# Motor_Driver_Sheet.net
KiCad netlist of a schematic drawn in Altium Designer
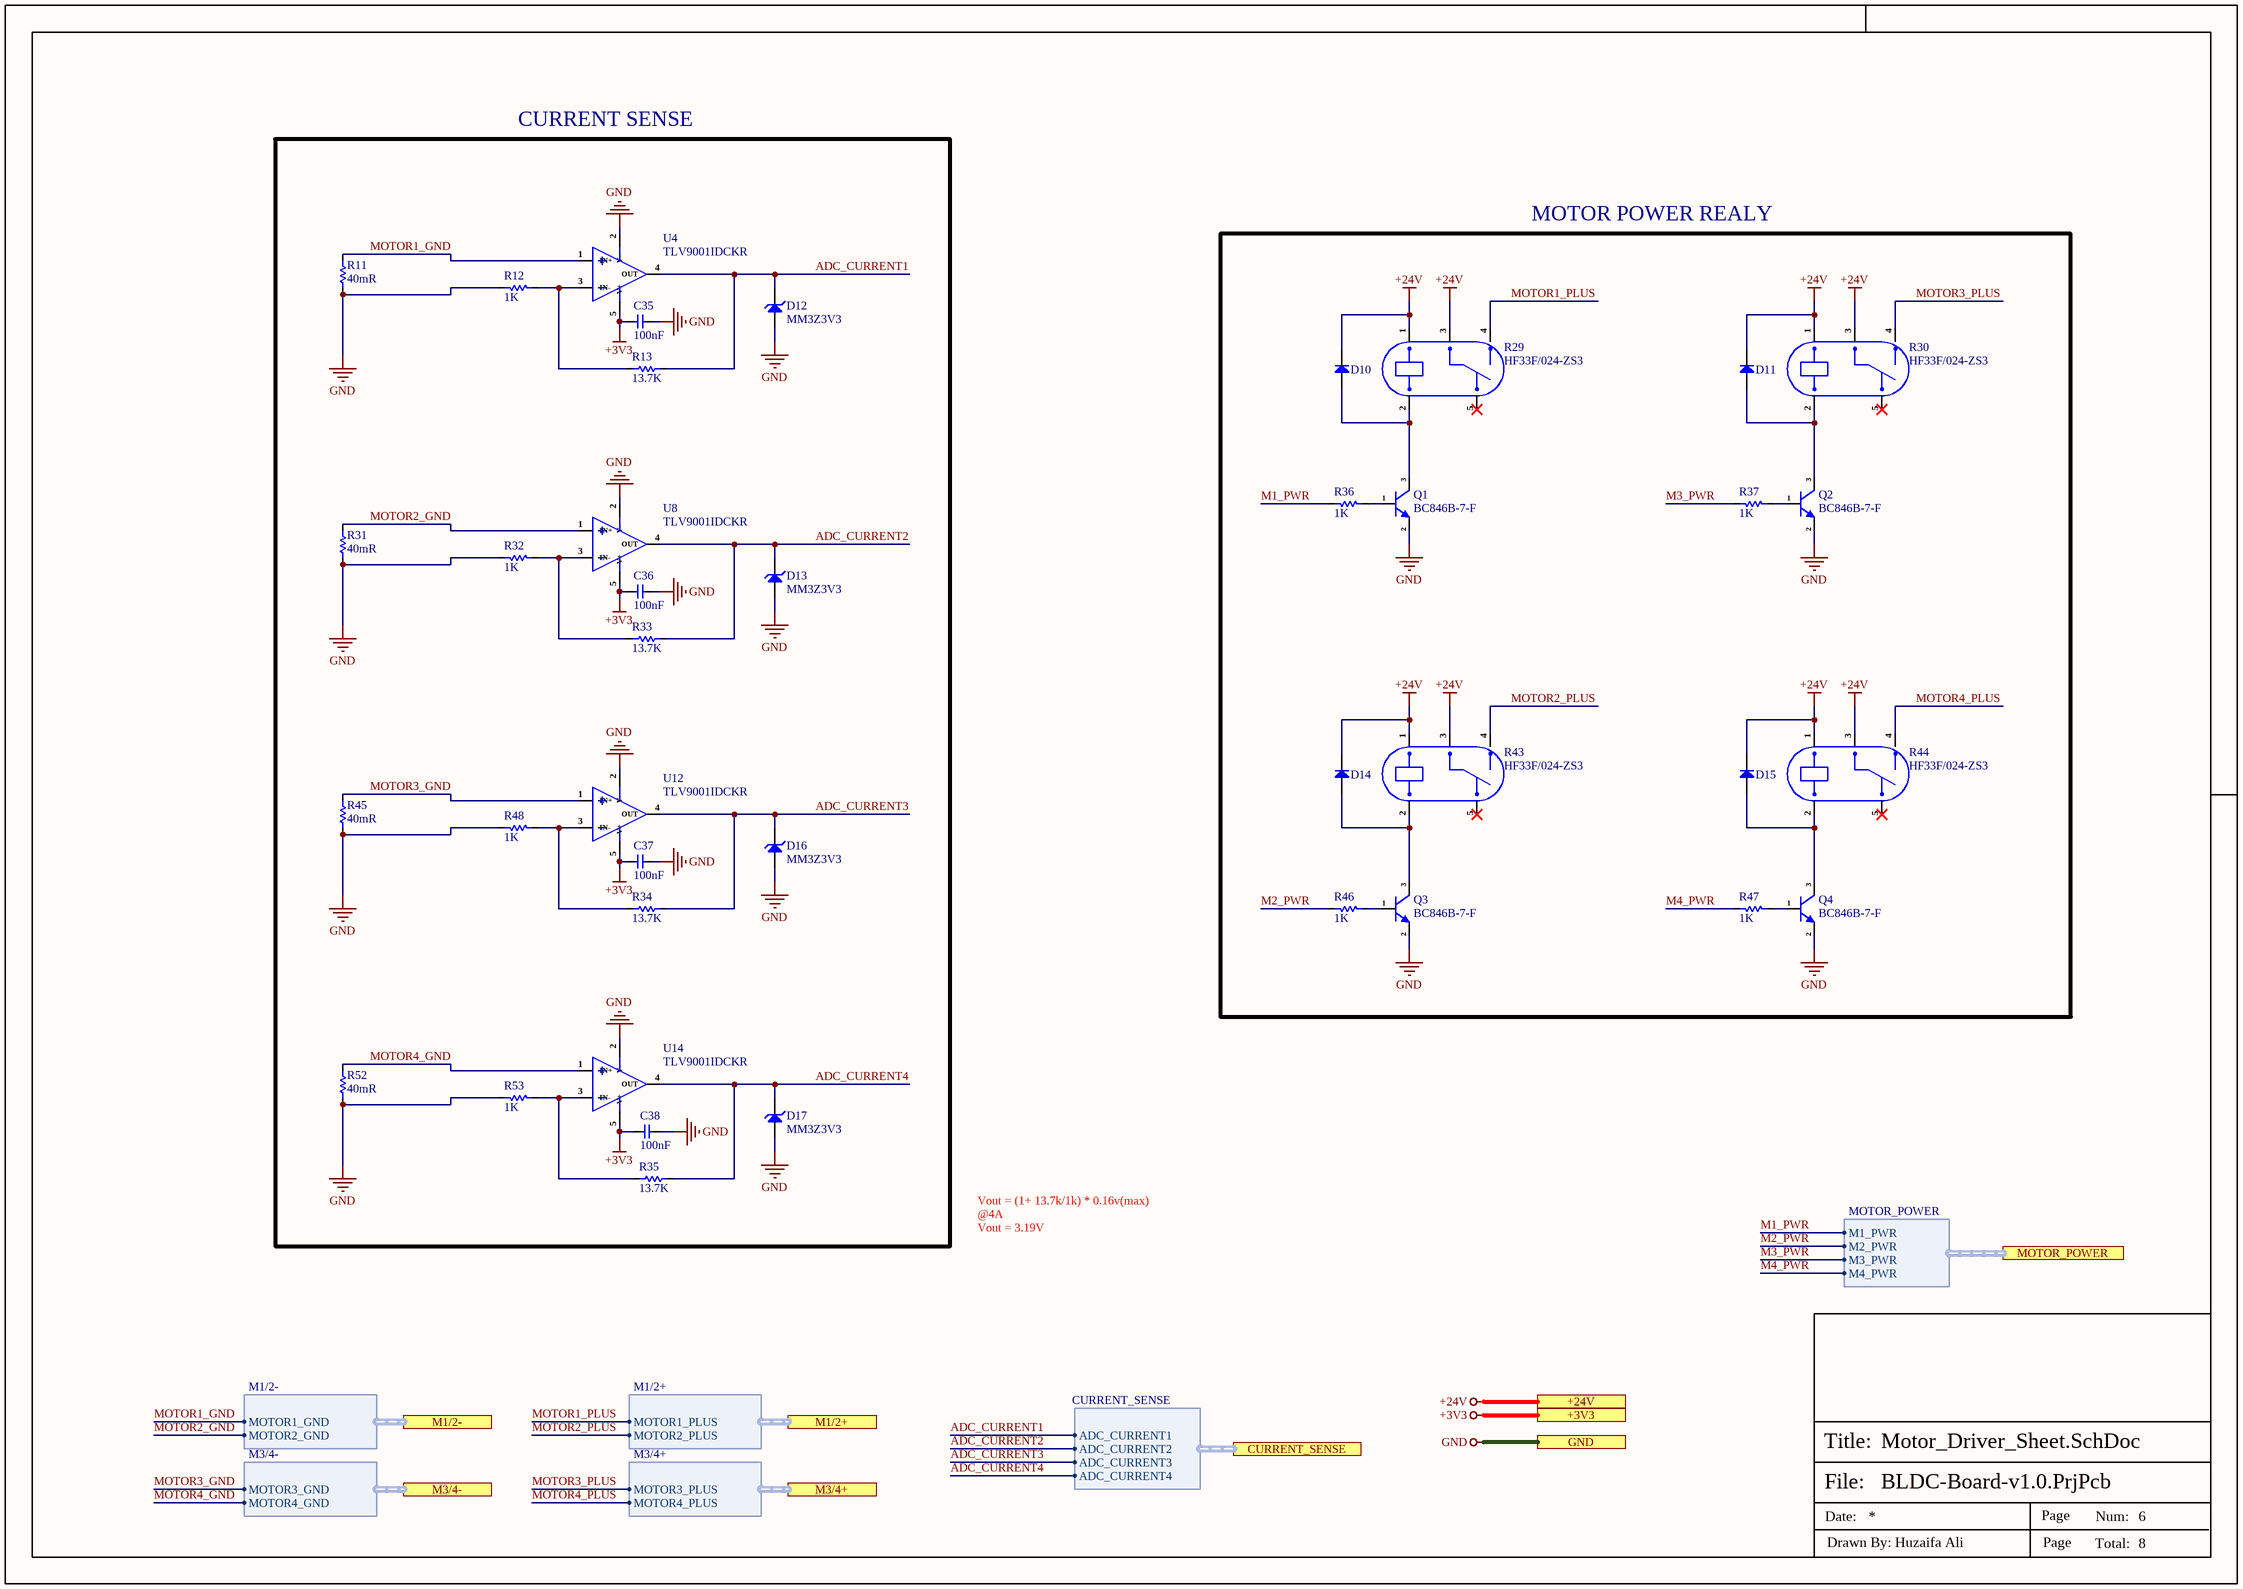
[diagram p0: Motor_Driver_Sheet.SchDoc]

(export (version "E")
  (design (tool "Eeschema 10.0.6"))
  (components
    (comp (ref "C35")
      (value "100nF")
      (footprint "cap-0402")
      (description "CAP CER 0.1UF 50V X7R 0402")
      (fields
        (field (name "MANUFACTURER") "TDK")
        (field (name "MANUFACTURER PART NUMBER") "C1005X7R1H104KT000F")
      )
      (libsource (lib "eSpark Libraries") (part "C1005X7R1H104KT000F"))
    )
    (comp (ref "C36")
      (value "100nF")
      (footprint "cap-0402")
      (description "CAP CER 0.1UF 50V X7R 0402")
      (fields
        (field (name "MANUFACTURER") "TDK")
        (field (name "MANUFACTURER PART NUMBER") "C1005X7R1H104KT000F")
      )
      (libsource (lib "eSpark Libraries") (part "C1005X7R1H104KT000F"))
    )
    (comp (ref "C37")
      (value "100nF")
      (footprint "cap-0402")
      (description "CAP CER 0.1UF 50V X7R 0402")
      (fields
        (field (name "MANUFACTURER") "TDK")
        (field (name "MANUFACTURER PART NUMBER") "C1005X7R1H104KT000F")
      )
      (libsource (lib "eSpark Libraries") (part "C1005X7R1H104KT000F"))
    )
    (comp (ref "C38")
      (value "100nF")
      (footprint "cap-0402")
      (description "CAP CER 0.1UF 50V X7R 0402")
      (fields
        (field (name "MANUFACTURER") "TDK")
        (field (name "MANUFACTURER PART NUMBER") "C1005X7R1H104KT000F")
      )
      (libsource (lib "eSpark Libraries") (part "C1005X7R1H104KT000F"))
    )
    (comp (ref "D10")
      (value "1N4148WS-7-F")
      (footprint "SOD-323")
      (description "DIODE GEN PURP 75V 150MA SOD323")
      (fields (field (name "MANUFACTURER") "Diodes") (field (name "VOLTAGE") "75V"))
      (libsource (lib "eSpark Libraries") (part "1N4148WS-7-F"))
    )
    (comp (ref "D11")
      (value "1N4148WS-7-F")
      (footprint "SOD-323")
      (description "DIODE GEN PURP 75V 150MA SOD323")
      (fields (field (name "MANUFACTURER") "Diodes") (field (name "VOLTAGE") "75V"))
      (libsource (lib "eSpark Libraries") (part "1N4148WS-7-F"))
    )
    (comp (ref "D12")
      (value "MM3Z3V3")
      (footprint "SOD-323")
      (description "±5% Single 3.1V~3.5V 300mW 3.3V SOD-323 Zener Diodes ROHS")
      (fields (field (name "MANUFACTURER") "JSMSEMI") (field (name "LCSC PART NUMBER") "C123917"))
      (libsource (lib "eSpark Libraries") (part "MM3Z3V3"))
    )
    (comp (ref "D13")
      (value "MM3Z3V3")
      (footprint "SOD-323")
      (description "±5% Single 3.1V~3.5V 300mW 3.3V SOD-323 Zener Diodes ROHS")
      (fields (field (name "MANUFACTURER") "JSMSEMI") (field (name "LCSC PART NUMBER") "C123917"))
      (libsource (lib "eSpark Libraries") (part "MM3Z3V3"))
    )
    (comp (ref "D14")
      (value "1N4148WS-7-F")
      (footprint "SOD-323")
      (description "DIODE GEN PURP 75V 150MA SOD323")
      (fields (field (name "MANUFACTURER") "Diodes") (field (name "VOLTAGE") "75V"))
      (libsource (lib "eSpark Libraries") (part "1N4148WS-7-F"))
    )
    (comp (ref "D15")
      (value "1N4148WS-7-F")
      (footprint "SOD-323")
      (description "DIODE GEN PURP 75V 150MA SOD323")
      (fields (field (name "MANUFACTURER") "Diodes") (field (name "VOLTAGE") "75V"))
      (libsource (lib "eSpark Libraries") (part "1N4148WS-7-F"))
    )
    (comp (ref "D16")
      (value "MM3Z3V3")
      (footprint "SOD-323")
      (description "±5% Single 3.1V~3.5V 300mW 3.3V SOD-323 Zener Diodes ROHS")
      (fields (field (name "MANUFACTURER") "JSMSEMI") (field (name "LCSC PART NUMBER") "C123917"))
      (libsource (lib "eSpark Libraries") (part "MM3Z3V3"))
    )
    (comp (ref "D17")
      (value "MM3Z3V3")
      (footprint "SOD-323")
      (description "±5% Single 3.1V~3.5V 300mW 3.3V SOD-323 Zener Diodes ROHS")
      (fields (field (name "MANUFACTURER") "JSMSEMI") (field (name "LCSC PART NUMBER") "C123917"))
      (libsource (lib "eSpark Libraries") (part "MM3Z3V3"))
    )
    (comp (ref "Q1")
      (value "BC846B-7-F")
      (footprint "SOT-23")
      (description "TRANS NPN 65V 0.1A SOT23-3")
      (fields (field (name "MANUFACTURER") "Diodes") (field (name "LCSC PART NUMBER") "C183643"))
      (libsource (lib "eSpark Libraries") (part "BC846B-7-F"))
    )
    (comp (ref "Q2")
      (value "BC846B-7-F")
      (footprint "SOT-23")
      (description "TRANS NPN 65V 0.1A SOT23-3")
      (fields (field (name "MANUFACTURER") "Diodes") (field (name "LCSC PART NUMBER") "C183643"))
      (libsource (lib "eSpark Libraries") (part "BC846B-7-F"))
    )
    (comp (ref "Q3")
      (value "BC846B-7-F")
      (footprint "SOT-23")
      (description "TRANS NPN 65V 0.1A SOT23-3")
      (fields (field (name "MANUFACTURER") "Diodes") (field (name "LCSC PART NUMBER") "C183643"))
      (libsource (lib "eSpark Libraries") (part "BC846B-7-F"))
    )
    (comp (ref "Q4")
      (value "BC846B-7-F")
      (footprint "SOT-23")
      (description "TRANS NPN 65V 0.1A SOT23-3")
      (fields (field (name "MANUFACTURER") "Diodes") (field (name "LCSC PART NUMBER") "C183643"))
      (libsource (lib "eSpark Libraries") (part "BC846B-7-F"))
    )
    (comp (ref "R11")
      (value "40mR")
      (footprint "Res-1206")
      (fields
        (field (name "MANUFACTURER") "RALEC")
        (field (name "MANUFACTURER PART NUMBER") "LR1206-21R040F4")
        (field (name "LCSC PART NUMBER") "C2681030")
      )
      (libsource (lib "eSpark Libraries") (part "LR1206-21R040F4"))
    )
    (comp (ref "R12")
      (value "1K")
      (footprint "Res-0402")
      (description "RES SMD 1K OHM 1% 1/5W 0402")
      (fields
        (field (name "MANUFACTURER") "Vishay Dale")
        (field (name "MANUFACTURER PART NUMBER") "CRCW04021K00FKEDHP")
      )
      (libsource (lib "eSpark Libraries") (part "CRCW04021K00FKEDHP"))
    )
    (comp (ref "R13")
      (value "13.7K")
      (footprint "Res-0603")
      (description "RES SMD 13.7KOHM 0.1% 1/10W 0603")
      (fields
        (field (name "MANUFACTURER") "Yageo")
        (field (name "MANUFACTURER PART NUMBER") "AT0603BRD0713K7L")
      )
      (libsource (lib "eSpark Libraries") (part "AT0603BRD0713K7L"))
    )
    (comp (ref "R29")
      (value "HF33F/024-ZS3")
      (footprint "HF33F/024-ZS3")
      (description "24V 10A SPDT (1 Form C) Plugin,10.2x20.5mm Power Relays ROHS")
      (fields
        (field (name "MANUFACTURER") "HF(Xiamen Hongfa Electroacoustic)")
        (field (name "LCSC PART NUMBER") "C36391")
      )
      (libsource (lib "eSpark Libraries") (part "HF33F/024-ZS3"))
    )
    (comp (ref "R30")
      (value "HF33F/024-ZS3")
      (footprint "HF33F/024-ZS3")
      (description "24V 10A SPDT (1 Form C) Plugin,10.2x20.5mm Power Relays ROHS")
      (fields
        (field (name "MANUFACTURER") "HF(Xiamen Hongfa Electroacoustic)")
        (field (name "LCSC PART NUMBER") "C36391")
      )
      (libsource (lib "eSpark Libraries") (part "HF33F/024-ZS3"))
    )
    (comp (ref "R31")
      (value "40mR")
      (footprint "Res-1206")
      (fields
        (field (name "MANUFACTURER") "RALEC")
        (field (name "MANUFACTURER PART NUMBER") "LR1206-21R040F4")
        (field (name "LCSC PART NUMBER") "C2681030")
      )
      (libsource (lib "eSpark Libraries") (part "LR1206-21R040F4"))
    )
    (comp (ref "R32")
      (value "1K")
      (footprint "Res-0402")
      (description "RES SMD 1K OHM 1% 1/5W 0402")
      (fields
        (field (name "MANUFACTURER") "Vishay Dale")
        (field (name "MANUFACTURER PART NUMBER") "CRCW04021K00FKEDHP")
      )
      (libsource (lib "eSpark Libraries") (part "CRCW04021K00FKEDHP"))
    )
    (comp (ref "R33")
      (value "13.7K")
      (footprint "Res-0603")
      (description "RES SMD 13.7KOHM 0.1% 1/10W 0603")
      (fields
        (field (name "MANUFACTURER") "Yageo")
        (field (name "MANUFACTURER PART NUMBER") "AT0603BRD0713K7L")
      )
      (libsource (lib "eSpark Libraries") (part "AT0603BRD0713K7L"))
    )
    (comp (ref "R34")
      (value "13.7K")
      (footprint "Res-0603")
      (description "RES SMD 13.7KOHM 0.1% 1/10W 0603")
      (fields
        (field (name "MANUFACTURER") "Yageo")
        (field (name "MANUFACTURER PART NUMBER") "AT0603BRD0713K7L")
      )
      (libsource (lib "eSpark Libraries") (part "AT0603BRD0713K7L"))
    )
    (comp (ref "R35")
      (value "13.7K")
      (footprint "Res-0603")
      (description "RES SMD 13.7KOHM 0.1% 1/10W 0603")
      (fields
        (field (name "MANUFACTURER") "Yageo")
        (field (name "MANUFACTURER PART NUMBER") "AT0603BRD0713K7L")
      )
      (libsource (lib "eSpark Libraries") (part "AT0603BRD0713K7L"))
    )
    (comp (ref "R36")
      (value "1K")
      (footprint "Res-0402")
      (description "RES SMD 1K OHM 1% 1/5W 0402")
      (fields
        (field (name "MANUFACTURER") "Vishay Dale")
        (field (name "MANUFACTURER PART NUMBER") "CRCW04021K00FKEDHP")
      )
      (libsource (lib "eSpark Libraries") (part "CRCW04021K00FKEDHP"))
    )
    (comp (ref "R37")
      (value "1K")
      (footprint "Res-0402")
      (description "RES SMD 1K OHM 1% 1/5W 0402")
      (fields
        (field (name "MANUFACTURER") "Vishay Dale")
        (field (name "MANUFACTURER PART NUMBER") "CRCW04021K00FKEDHP")
      )
      (libsource (lib "eSpark Libraries") (part "CRCW04021K00FKEDHP"))
    )
    (comp (ref "R43")
      (value "HF33F/024-ZS3")
      (footprint "HF33F/024-ZS3")
      (description "24V 10A SPDT (1 Form C) Plugin,10.2x20.5mm Power Relays ROHS")
      (fields
        (field (name "MANUFACTURER") "HF(Xiamen Hongfa Electroacoustic)")
        (field (name "LCSC PART NUMBER") "C36391")
      )
      (libsource (lib "eSpark Libraries") (part "HF33F/024-ZS3"))
    )
    (comp (ref "R44")
      (value "HF33F/024-ZS3")
      (footprint "HF33F/024-ZS3")
      (description "24V 10A SPDT (1 Form C) Plugin,10.2x20.5mm Power Relays ROHS")
      (fields
        (field (name "MANUFACTURER") "HF(Xiamen Hongfa Electroacoustic)")
        (field (name "LCSC PART NUMBER") "C36391")
      )
      (libsource (lib "eSpark Libraries") (part "HF33F/024-ZS3"))
    )
    (comp (ref "R45")
      (value "40mR")
      (footprint "Res-1206")
      (fields
        (field (name "MANUFACTURER") "RALEC")
        (field (name "MANUFACTURER PART NUMBER") "LR1206-21R040F4")
        (field (name "LCSC PART NUMBER") "C2681030")
      )
      (libsource (lib "eSpark Libraries") (part "LR1206-21R040F4"))
    )
    (comp (ref "R46")
      (value "1K")
      (footprint "Res-0402")
      (description "RES SMD 1K OHM 1% 1/5W 0402")
      (fields
        (field (name "MANUFACTURER") "Vishay Dale")
        (field (name "MANUFACTURER PART NUMBER") "CRCW04021K00FKEDHP")
      )
      (libsource (lib "eSpark Libraries") (part "CRCW04021K00FKEDHP"))
    )
    (comp (ref "R47")
      (value "1K")
      (footprint "Res-0402")
      (description "RES SMD 1K OHM 1% 1/5W 0402")
      (fields
        (field (name "MANUFACTURER") "Vishay Dale")
        (field (name "MANUFACTURER PART NUMBER") "CRCW04021K00FKEDHP")
      )
      (libsource (lib "eSpark Libraries") (part "CRCW04021K00FKEDHP"))
    )
    (comp (ref "R48")
      (value "1K")
      (footprint "Res-0402")
      (description "RES SMD 1K OHM 1% 1/5W 0402")
      (fields
        (field (name "MANUFACTURER") "Vishay Dale")
        (field (name "MANUFACTURER PART NUMBER") "CRCW04021K00FKEDHP")
      )
      (libsource (lib "eSpark Libraries") (part "CRCW04021K00FKEDHP"))
    )
    (comp (ref "R52")
      (value "40mR")
      (footprint "Res-1206")
      (fields
        (field (name "MANUFACTURER") "RALEC")
        (field (name "MANUFACTURER PART NUMBER") "LR1206-21R040F4")
        (field (name "LCSC PART NUMBER") "C2681030")
      )
      (libsource (lib "eSpark Libraries") (part "LR1206-21R040F4"))
    )
    (comp (ref "R53")
      (value "1K")
      (footprint "Res-0402")
      (description "RES SMD 1K OHM 1% 1/5W 0402")
      (fields
        (field (name "MANUFACTURER") "Vishay Dale")
        (field (name "MANUFACTURER PART NUMBER") "CRCW04021K00FKEDHP")
      )
      (libsource (lib "eSpark Libraries") (part "CRCW04021K00FKEDHP"))
    )
    (comp (ref "U4")
      (value "TLV9001IDCKR")
      (footprint "SC-70-5")
      (description "IC CMOS 1 CIRCUIT SC70-5")
      (fields (field (name "MANUFACTURER") "Texas Instruments") (field (name "LCSC PART NUMBER") "C398362"))
      (libsource (lib "eSpark Libraries") (part "TLV9001IDCKR"))
    )
    (comp (ref "U8")
      (value "TLV9001IDCKR")
      (footprint "SC-70-5")
      (description "IC CMOS 1 CIRCUIT SC70-5")
      (fields (field (name "MANUFACTURER") "Texas Instruments") (field (name "LCSC PART NUMBER") "C398362"))
      (libsource (lib "eSpark Libraries") (part "TLV9001IDCKR"))
    )
    (comp (ref "U12")
      (value "TLV9001IDCKR")
      (footprint "SC-70-5")
      (description "IC CMOS 1 CIRCUIT SC70-5")
      (fields (field (name "MANUFACTURER") "Texas Instruments") (field (name "LCSC PART NUMBER") "C398362"))
      (libsource (lib "eSpark Libraries") (part "TLV9001IDCKR"))
    )
    (comp (ref "U14")
      (value "TLV9001IDCKR")
      (footprint "SC-70-5")
      (description "IC CMOS 1 CIRCUIT SC70-5")
      (fields (field (name "MANUFACTURER") "Texas Instruments") (field (name "LCSC PART NUMBER") "C398362"))
      (libsource (lib "eSpark Libraries") (part "TLV9001IDCKR"))
    )
  )
  (nets
    (net (code "7") (name "+3V3") (class "Default")
      (node (ref "C35") (pin "2") (pinfunction "2_2") (pintype "passive"))
      (node (ref "C36") (pin "2") (pinfunction "2_2") (pintype "passive"))
      (node (ref "C37") (pin "2") (pinfunction "2_2") (pintype "passive"))
      (node (ref "C38") (pin "2") (pinfunction "2_2") (pintype "passive"))
      (node (ref "U12") (pin "5") (pinfunction "V+_5") (pintype "power_in"))
      (node (ref "U14") (pin "5") (pinfunction "V+_5") (pintype "power_in"))
      (node (ref "U4") (pin "5") (pinfunction "V+_5") (pintype "power_in"))
      (node (ref "U8") (pin "5") (pinfunction "V+_5") (pintype "power_in"))
    )
    (net (code "8") (name "+24V") (class "Default")
      (node (ref "D10") (pin "1") (pinfunction "K_1") (pintype "passive"))
      (node (ref "D11") (pin "1") (pinfunction "K_1") (pintype "passive"))
      (node (ref "D14") (pin "1") (pinfunction "K_1") (pintype "passive"))
      (node (ref "D15") (pin "1") (pinfunction "K_1") (pintype "passive"))
      (node (ref "R29") (pin "1") (pinfunction "1_1") (pintype "passive"))
      (node (ref "R29") (pin "3") (pinfunction "3_3") (pintype "passive"))
      (node (ref "R30") (pin "1") (pinfunction "1_1") (pintype "passive"))
      (node (ref "R30") (pin "3") (pinfunction "3_3") (pintype "passive"))
      (node (ref "R43") (pin "1") (pinfunction "1_1") (pintype "passive"))
      (node (ref "R43") (pin "3") (pinfunction "3_3") (pintype "passive"))
      (node (ref "R44") (pin "1") (pinfunction "1_1") (pintype "passive"))
      (node (ref "R44") (pin "3") (pinfunction "3_3") (pintype "passive"))
    )
    (net (code "9") (name "/ADC_CURRENT1") (class "Default")
      (node (ref "D12") (pin "1") (pinfunction "K_1") (pintype "passive"))
      (node (ref "R13") (pin "2") (pinfunction "2_2") (pintype "passive"))
      (node (ref "U4") (pin "4") (pinfunction "OUT_4") (pintype "passive"))
    )
    (net (code "10") (name "/ADC_CURRENT2") (class "Default")
      (node (ref "D13") (pin "1") (pinfunction "K_1") (pintype "passive"))
      (node (ref "R33") (pin "2") (pinfunction "2_2") (pintype "passive"))
      (node (ref "U8") (pin "4") (pinfunction "OUT_4") (pintype "passive"))
    )
    (net (code "11") (name "/ADC_CURRENT3") (class "Default")
      (node (ref "D16") (pin "1") (pinfunction "K_1") (pintype "passive"))
      (node (ref "R34") (pin "2") (pinfunction "2_2") (pintype "passive"))
      (node (ref "U12") (pin "4") (pinfunction "OUT_4") (pintype "passive"))
    )
    (net (code "12") (name "/ADC_CURRENT4") (class "Default")
      (node (ref "D17") (pin "1") (pinfunction "K_1") (pintype "passive"))
      (node (ref "R35") (pin "2") (pinfunction "2_2") (pintype "passive"))
      (node (ref "U14") (pin "4") (pinfunction "OUT_4") (pintype "passive"))
    )
    (net (code "13") (name "/M1_PWR") (class "Default")
      (node (ref "R36") (pin "2") (pinfunction "2_2") (pintype "passive"))
    )
    (net (code "14") (name "/M2_PWR") (class "Default")
      (node (ref "R46") (pin "2") (pinfunction "2_2") (pintype "passive"))
    )
    (net (code "15") (name "/M3_PWR") (class "Default")
      (node (ref "R37") (pin "2") (pinfunction "2_2") (pintype "passive"))
    )
    (net (code "16") (name "/M4_PWR") (class "Default")
      (node (ref "R47") (pin "2") (pinfunction "2_2") (pintype "passive"))
    )
    (net (code "17") (name "/MOTOR1_GND") (class "Default")
      (node (ref "R11") (pin "2") (pinfunction "2_2") (pintype "passive"))
      (node (ref "U4") (pin "1") (pinfunction "IN+_1") (pintype "passive"))
    )
    (net (code "18") (name "/MOTOR1_PLUS") (class "Default")
      (node (ref "R29") (pin "4") (pinfunction "4_4") (pintype "passive"))
    )
    (net (code "19") (name "/MOTOR2_GND") (class "Default")
      (node (ref "R31") (pin "2") (pinfunction "2_2") (pintype "passive"))
      (node (ref "U8") (pin "1") (pinfunction "IN+_1") (pintype "passive"))
    )
    (net (code "20") (name "/MOTOR2_PLUS") (class "Default")
      (node (ref "R43") (pin "4") (pinfunction "4_4") (pintype "passive"))
    )
    (net (code "21") (name "/MOTOR3_GND") (class "Default")
      (node (ref "R45") (pin "2") (pinfunction "2_2") (pintype "passive"))
      (node (ref "U12") (pin "1") (pinfunction "IN+_1") (pintype "passive"))
    )
    (net (code "22") (name "/MOTOR3_PLUS") (class "Default")
      (node (ref "R30") (pin "4") (pinfunction "4_4") (pintype "passive"))
    )
    (net (code "23") (name "/MOTOR4_GND") (class "Default")
      (node (ref "R52") (pin "2") (pinfunction "2_2") (pintype "passive"))
      (node (ref "U14") (pin "1") (pinfunction "IN+_1") (pintype "passive"))
    )
    (net (code "24") (name "/MOTOR4_PLUS") (class "Default")
      (node (ref "R44") (pin "4") (pinfunction "4_4") (pintype "passive"))
    )
    (net (code "31") (name "GND") (class "Default")
      (node (ref "C35") (pin "1") (pinfunction "1_1") (pintype "passive"))
      (node (ref "C36") (pin "1") (pinfunction "1_1") (pintype "passive"))
      (node (ref "C37") (pin "1") (pinfunction "1_1") (pintype "passive"))
      (node (ref "C38") (pin "1") (pinfunction "1_1") (pintype "passive"))
      (node (ref "D12") (pin "2") (pinfunction "A_2") (pintype "passive"))
      (node (ref "D13") (pin "2") (pinfunction "A_2") (pintype "passive"))
      (node (ref "D16") (pin "2") (pinfunction "A_2") (pintype "passive"))
      (node (ref "D17") (pin "2") (pinfunction "A_2") (pintype "passive"))
      (node (ref "Q1") (pin "2") (pinfunction "E_2") (pintype "passive"))
      (node (ref "Q2") (pin "2") (pinfunction "E_2") (pintype "passive"))
      (node (ref "Q3") (pin "2") (pinfunction "E_2") (pintype "passive"))
      (node (ref "Q4") (pin "2") (pinfunction "E_2") (pintype "passive"))
      (node (ref "R11") (pin "1") (pinfunction "1_1") (pintype "passive"))
      (node (ref "R12") (pin "2") (pinfunction "2_2") (pintype "passive"))
      (node (ref "R31") (pin "1") (pinfunction "1_1") (pintype "passive"))
      (node (ref "R32") (pin "2") (pinfunction "2_2") (pintype "passive"))
      (node (ref "R45") (pin "1") (pinfunction "1_1") (pintype "passive"))
      (node (ref "R48") (pin "2") (pinfunction "2_2") (pintype "passive"))
      (node (ref "R52") (pin "1") (pinfunction "1_1") (pintype "passive"))
      (node (ref "R53") (pin "2") (pinfunction "2_2") (pintype "passive"))
      (node (ref "U12") (pin "2") (pinfunction "V-_2") (pintype "power_in"))
      (node (ref "U14") (pin "2") (pinfunction "V-_2") (pintype "power_in"))
      (node (ref "U4") (pin "2") (pinfunction "V-_2") (pintype "power_in"))
      (node (ref "U8") (pin "2") (pinfunction "V-_2") (pintype "power_in"))
    )
    (net (code "32") (name "Net-(D10-A)") (class "Default")
      (node (ref "D10") (pin "2") (pinfunction "A_2") (pintype "passive"))
      (node (ref "Q1") (pin "3") (pinfunction "C_3") (pintype "passive"))
      (node (ref "R29") (pin "2") (pinfunction "2_2") (pintype "passive"))
    )
    (net (code "33") (name "Net-(D11-A)") (class "Default")
      (node (ref "D11") (pin "2") (pinfunction "A_2") (pintype "passive"))
      (node (ref "Q2") (pin "3") (pinfunction "C_3") (pintype "passive"))
      (node (ref "R30") (pin "2") (pinfunction "2_2") (pintype "passive"))
    )
    (net (code "34") (name "Net-(D14-A)") (class "Default")
      (node (ref "D14") (pin "2") (pinfunction "A_2") (pintype "passive"))
      (node (ref "Q3") (pin "3") (pinfunction "C_3") (pintype "passive"))
      (node (ref "R43") (pin "2") (pinfunction "2_2") (pintype "passive"))
    )
    (net (code "35") (name "Net-(D15-A)") (class "Default")
      (node (ref "D15") (pin "2") (pinfunction "A_2") (pintype "passive"))
      (node (ref "Q4") (pin "3") (pinfunction "C_3") (pintype "passive"))
      (node (ref "R44") (pin "2") (pinfunction "2_2") (pintype "passive"))
    )
    (net (code "36") (name "Net-(Q1-B)") (class "Default")
      (node (ref "Q1") (pin "1") (pinfunction "B_1") (pintype "passive"))
      (node (ref "R36") (pin "1") (pinfunction "1_1") (pintype "passive"))
    )
    (net (code "37") (name "Net-(Q2-B)") (class "Default")
      (node (ref "Q2") (pin "1") (pinfunction "B_1") (pintype "passive"))
      (node (ref "R37") (pin "1") (pinfunction "1_1") (pintype "passive"))
    )
    (net (code "38") (name "Net-(Q3-B)") (class "Default")
      (node (ref "Q3") (pin "1") (pinfunction "B_1") (pintype "passive"))
      (node (ref "R46") (pin "1") (pinfunction "1_1") (pintype "passive"))
    )
    (net (code "39") (name "Net-(Q4-B)") (class "Default")
      (node (ref "Q4") (pin "1") (pinfunction "B_1") (pintype "passive"))
      (node (ref "R47") (pin "1") (pinfunction "1_1") (pintype "passive"))
    )
    (net (code "40") (name "Net-(U4-IN-)") (class "Default")
      (node (ref "R12") (pin "1") (pinfunction "1_1") (pintype "passive"))
      (node (ref "R13") (pin "1") (pinfunction "1_1") (pintype "passive"))
      (node (ref "U4") (pin "3") (pinfunction "IN-_3") (pintype "passive"))
    )
    (net (code "41") (name "Net-(U8-IN-)") (class "Default")
      (node (ref "R32") (pin "1") (pinfunction "1_1") (pintype "passive"))
      (node (ref "R33") (pin "1") (pinfunction "1_1") (pintype "passive"))
      (node (ref "U8") (pin "3") (pinfunction "IN-_3") (pintype "passive"))
    )
    (net (code "42") (name "Net-(U12-IN-)") (class "Default")
      (node (ref "R34") (pin "1") (pinfunction "1_1") (pintype "passive"))
      (node (ref "R48") (pin "1") (pinfunction "1_1") (pintype "passive"))
      (node (ref "U12") (pin "3") (pinfunction "IN-_3") (pintype "passive"))
    )
    (net (code "43") (name "Net-(U14-IN-)") (class "Default")
      (node (ref "R35") (pin "1") (pinfunction "1_1") (pintype "passive"))
      (node (ref "R53") (pin "1") (pinfunction "1_1") (pintype "passive"))
      (node (ref "U14") (pin "3") (pinfunction "IN-_3") (pintype "passive"))
    )
    (net (code "44") (name "unconnected-(R29-Pad5)") (class "Default")
      (node (ref "R29") (pin "5") (pinfunction "5_5") (pintype "passive+no_connect"))
    )
    (net (code "45") (name "unconnected-(R30-Pad5)") (class "Default")
      (node (ref "R30") (pin "5") (pinfunction "5_5") (pintype "passive+no_connect"))
    )
    (net (code "46") (name "unconnected-(R43-Pad5)") (class "Default")
      (node (ref "R43") (pin "5") (pinfunction "5_5") (pintype "passive+no_connect"))
    )
    (net (code "47") (name "unconnected-(R44-Pad5)") (class "Default")
      (node (ref "R44") (pin "5") (pinfunction "5_5") (pintype "passive+no_connect"))
    )
  )
)
